# schematic.net
KiCad netlist of a schematic drawn in EasyEDA
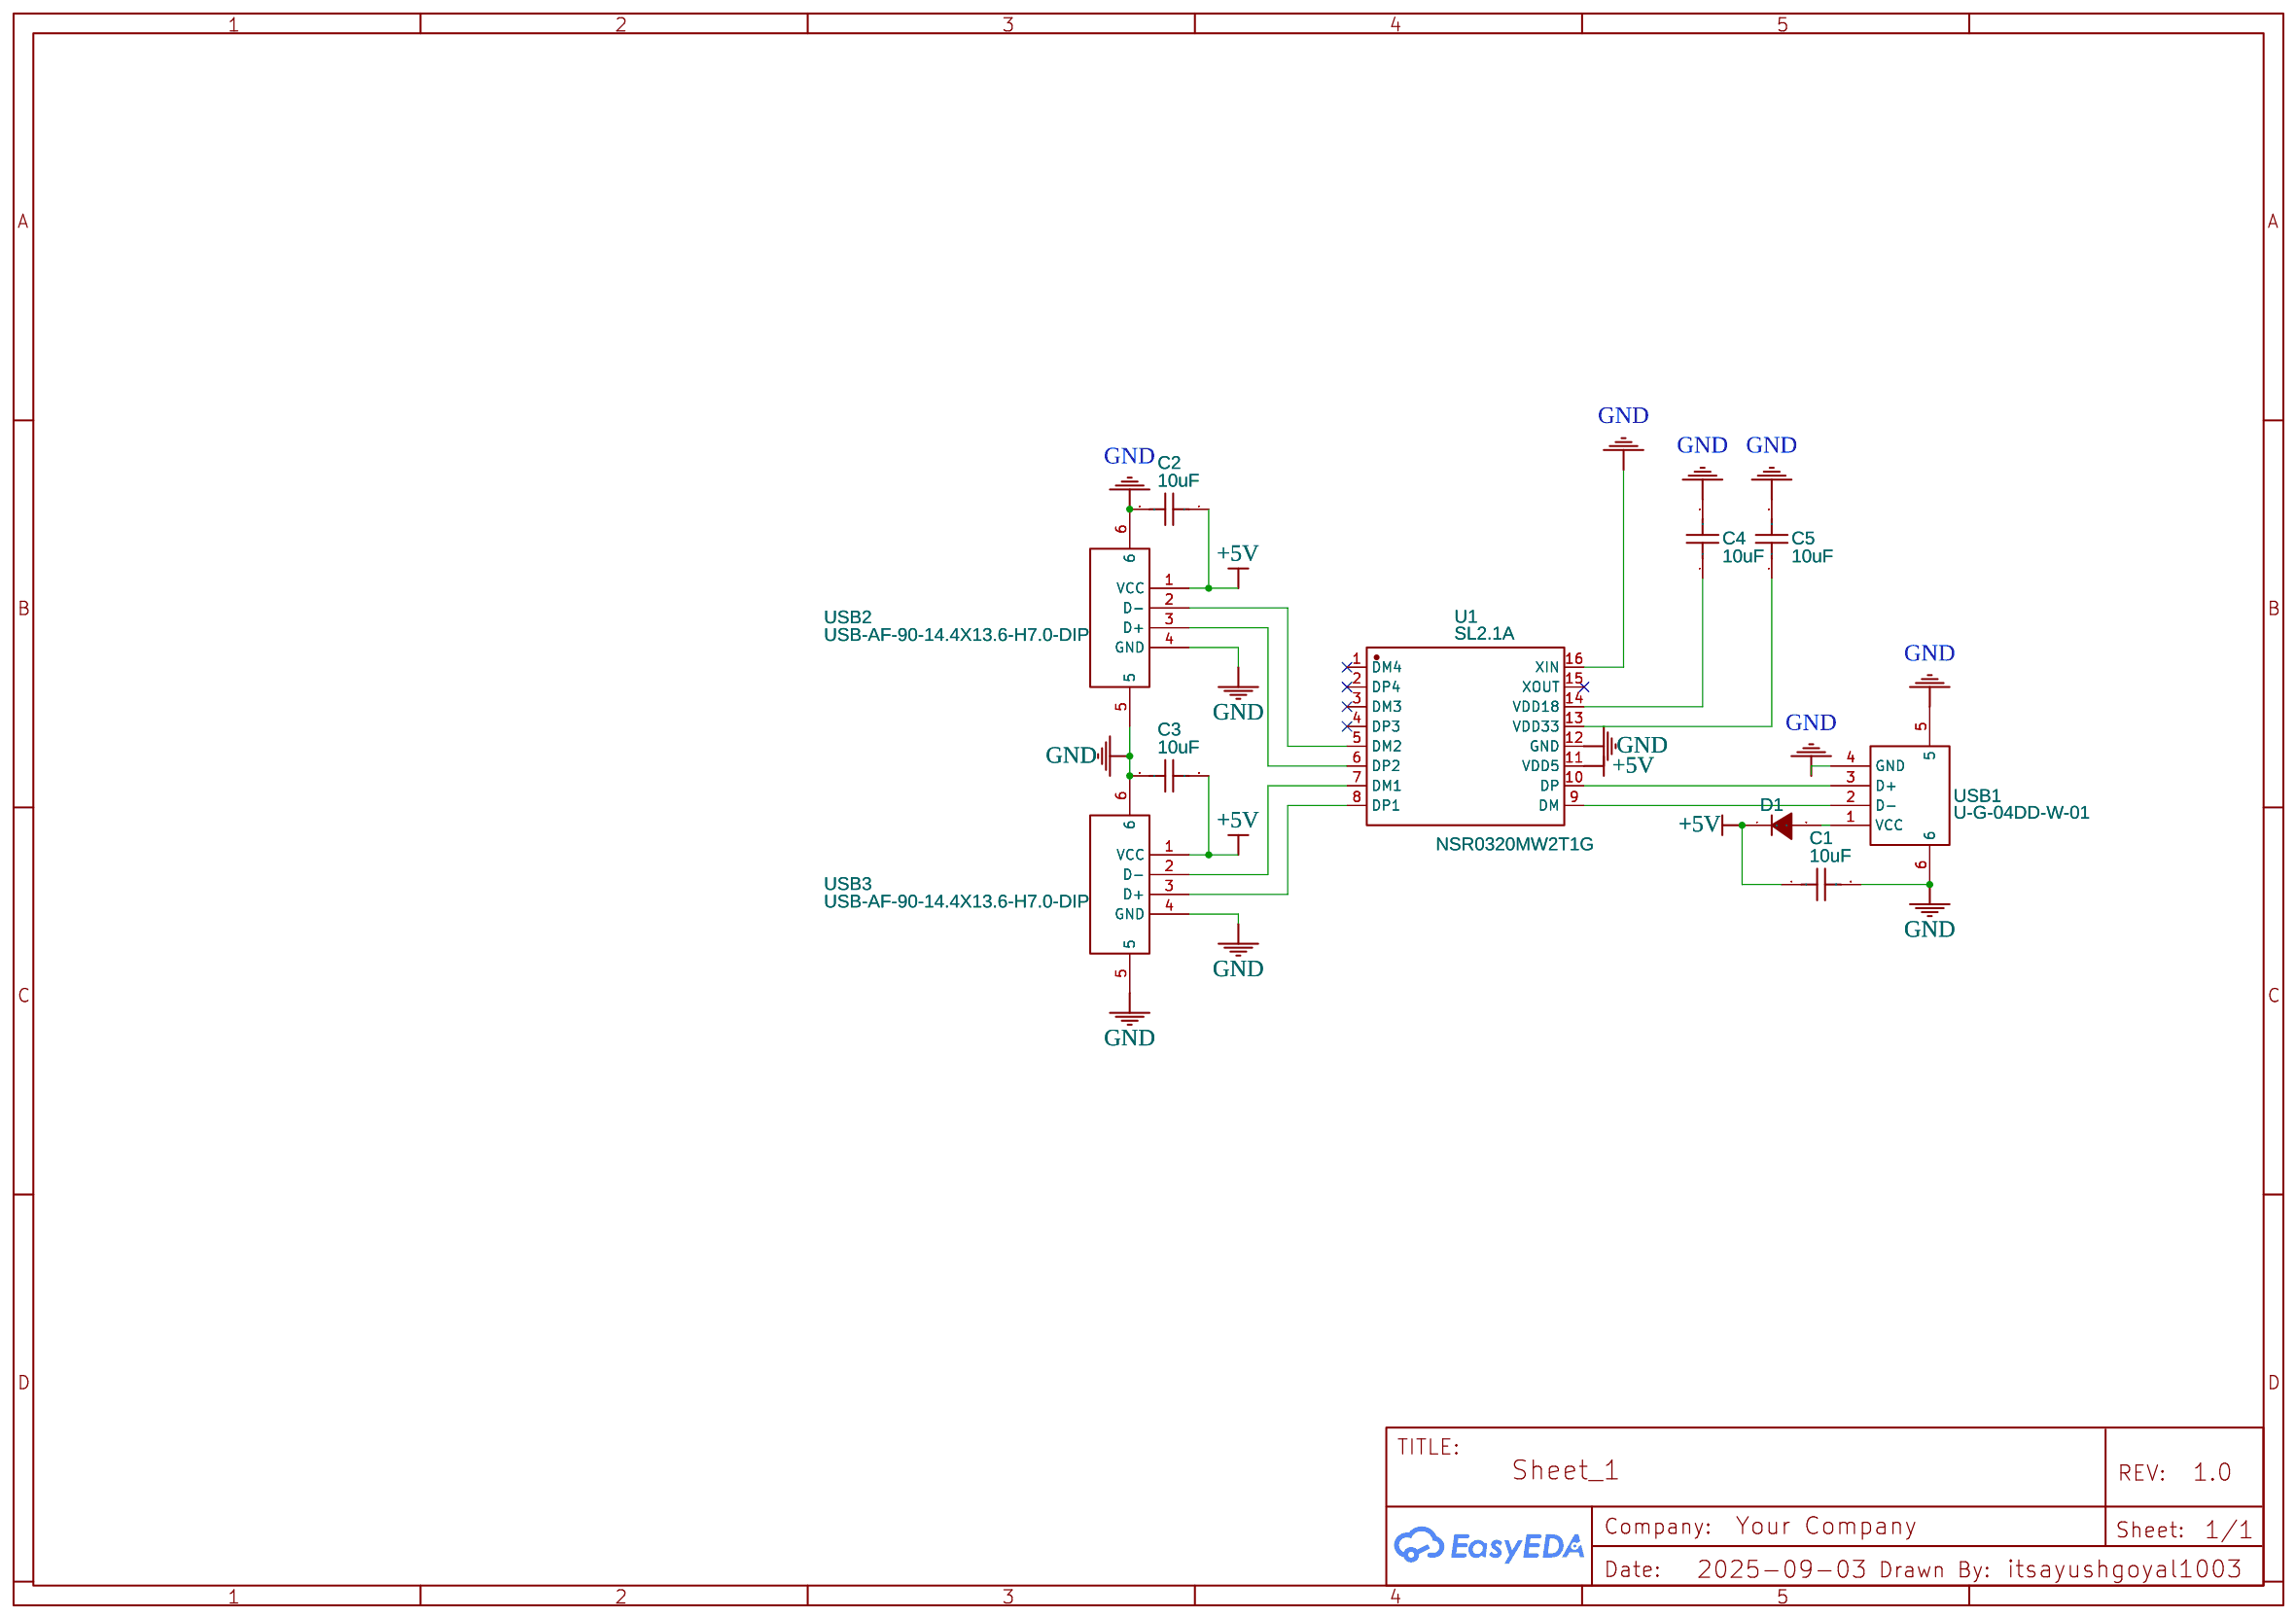
[diagram p0: schematic sheet]

(export (version "E")
  (design (tool "Eeschema 10.0.6"))
  (components
    (comp (ref "C1")
      (value "10uF")
      (fields
        (field (name "Manufacturer Part") "CL10A106KP8NNNC")
        (field (name "Manufacturer") "SAMSUNG(三星)")
      )
      (libsource (lib "") (part "CL10A106KP8NNNC"))
    )
    (comp (ref "C2")
      (value "10uF")
      (fields
        (field (name "Manufacturer Part") "CL10A106KP8NNNC")
        (field (name "Manufacturer") "SAMSUNG(三星)")
      )
      (libsource (lib "") (part "CL10A106KP8NNNC_1"))
    )
    (comp (ref "C3")
      (value "10uF")
      (fields
        (field (name "Manufacturer Part") "CL10A106KP8NNNC")
        (field (name "Manufacturer") "SAMSUNG(三星)")
      )
      (libsource (lib "") (part "CL10A106KP8NNNC"))
    )
    (comp (ref "C4")
      (value "10uF")
      (fields
        (field (name "Manufacturer Part") "CL10A106KP8NNNC")
        (field (name "Manufacturer") "SAMSUNG(三星)")
      )
      (libsource (lib "") (part "CL10A106KP8NNNC_2"))
    )
    (comp (ref "C5")
      (value "10uF")
      (fields
        (field (name "Manufacturer Part") "CL10A106KP8NNNC")
        (field (name "Manufacturer") "SAMSUNG(三星)")
      )
      (libsource (lib "") (part "CL10A106KP8NNNC_2"))
    )
    (comp (ref "D1")
      (value "NSR0320MW2T1G")
      (fields (field (name "Manufacturer") "onsemi(安森美)"))
      (libsource (lib "") (part "NSR0320MW2T1G"))
    )
    (comp (ref "U1")
      (value "SL2.1A")
      (fields (field (name "Manufacturer") "CoreChips(和芯润德)"))
      (libsource (lib "") (part "SL2.1A"))
    )
    (comp (ref "USB1")
      (value "U-G-04DD-W-01")
      (fields (field (name "Manufacturer Part") "U-G-O4DD-W-1") (field (name "Manufacturer") "韩国韩荣"))
      (libsource (lib "") (part "U-G-04DD-W-01"))
    )
    (comp (ref "USB2")
      (value "USB-AF-90-14.4X13.6-H7.0-DIP")
      (fields (field (name "Manufacturer Part") "903-131A1011D10100") (field (name "Manufacturer") "精拓金"))
      (libsource (lib "") (part "USB-AF-90-14.4X13.6-H7.0-DIP"))
    )
    (comp (ref "USB3")
      (value "USB-AF-90-14.4X13.6-H7.0-DIP")
      (fields (field (name "Manufacturer Part") "903-131A1011D10100") (field (name "Manufacturer") "精拓金"))
      (libsource (lib "") (part "USB-AF-90-14.4X13.6-H7.0-DIP"))
    )
  )
  (nets
    (net (code "1") (name "+5V") (class "Default")
      (node (ref "C1") (pin "1") (pinfunction "1_1") (pintype "unspecified"))
      (node (ref "C2") (pin "1") (pinfunction "1_1") (pintype "unspecified"))
      (node (ref "C3") (pin "2") (pinfunction "2_2") (pintype "unspecified"))
      (node (ref "D1") (pin "1") (pinfunction "C_1") (pintype "unspecified"))
      (node (ref "U1") (pin "11") (pinfunction "VDD5_11") (pintype "unspecified"))
      (node (ref "USB2") (pin "1") (pinfunction "VCC_1") (pintype "unspecified"))
      (node (ref "USB3") (pin "1") (pinfunction "VCC_1") (pintype "unspecified"))
    )
    (net (code "2") (name "GND") (class "Default")
      (node (ref "C1") (pin "2") (pinfunction "2_2") (pintype "unspecified"))
      (node (ref "C2") (pin "2") (pinfunction "2_2") (pintype "unspecified"))
      (node (ref "C3") (pin "1") (pinfunction "1_1") (pintype "unspecified"))
      (node (ref "C4") (pin "2") (pinfunction "2_2") (pintype "unspecified"))
      (node (ref "C5") (pin "2") (pinfunction "2_2") (pintype "unspecified"))
      (node (ref "U1") (pin "12") (pinfunction "GND_12") (pintype "unspecified"))
      (node (ref "U1") (pin "16") (pinfunction "XIN_16") (pintype "unspecified"))
      (node (ref "USB1") (pin "4") (pinfunction "GND_4") (pintype "unspecified"))
      (node (ref "USB1") (pin "5") (pinfunction "5_5") (pintype "unspecified"))
      (node (ref "USB1") (pin "6") (pinfunction "6_6") (pintype "unspecified"))
      (node (ref "USB2") (pin "4") (pinfunction "GND_4") (pintype "unspecified"))
      (node (ref "USB2") (pin "5") (pinfunction "5_5") (pintype "unspecified"))
      (node (ref "USB2") (pin "6") (pinfunction "6_6") (pintype "unspecified"))
      (node (ref "USB3") (pin "4") (pinfunction "GND_4") (pintype "unspecified"))
      (node (ref "USB3") (pin "5") (pinfunction "5_5") (pintype "unspecified"))
      (node (ref "USB3") (pin "6") (pinfunction "6_6") (pintype "unspecified"))
    )
    (net (code "3") (name "Net-(D1-A)") (class "Default")
      (node (ref "D1") (pin "2") (pinfunction "A_2") (pintype "unspecified"))
      (node (ref "USB1") (pin "1") (pinfunction "VCC_1") (pintype "unspecified"))
    )
    (net (code "4") (name "Net-(U1-DM)") (class "Default")
      (node (ref "U1") (pin "9") (pinfunction "DM_9") (pintype "unspecified"))
      (node (ref "USB1") (pin "2") (pinfunction "D-_2") (pintype "unspecified"))
    )
    (net (code "5") (name "Net-(U1-DM1)") (class "Default")
      (node (ref "U1") (pin "7") (pinfunction "DM1_7") (pintype "unspecified"))
      (node (ref "USB3") (pin "2") (pinfunction "D-_2") (pintype "unspecified"))
    )
    (net (code "6") (name "Net-(U1-DM2)") (class "Default")
      (node (ref "U1") (pin "5") (pinfunction "DM2_5") (pintype "unspecified"))
      (node (ref "USB2") (pin "2") (pinfunction "D-_2") (pintype "unspecified"))
    )
    (net (code "7") (name "Net-(U1-DP)") (class "Default")
      (node (ref "U1") (pin "10") (pinfunction "DP_10") (pintype "unspecified"))
      (node (ref "USB1") (pin "3") (pinfunction "D+_3") (pintype "unspecified"))
    )
    (net (code "8") (name "Net-(U1-DP1)") (class "Default")
      (node (ref "U1") (pin "8") (pinfunction "DP1_8") (pintype "unspecified"))
      (node (ref "USB3") (pin "3") (pinfunction "D+_3") (pintype "unspecified"))
    )
    (net (code "9") (name "Net-(U1-DP2)") (class "Default")
      (node (ref "U1") (pin "6") (pinfunction "DP2_6") (pintype "unspecified"))
      (node (ref "USB2") (pin "3") (pinfunction "D+_3") (pintype "unspecified"))
    )
    (net (code "10") (name "Net-(U1-VDD18)") (class "Default")
      (node (ref "C4") (pin "1") (pinfunction "1_1") (pintype "unspecified"))
      (node (ref "U1") (pin "14") (pinfunction "VDD18_14") (pintype "unspecified"))
    )
    (net (code "11") (name "Net-(U1-VDD33)") (class "Default")
      (node (ref "C5") (pin "1") (pinfunction "1_1") (pintype "unspecified"))
      (node (ref "U1") (pin "13") (pinfunction "VDD33_13") (pintype "unspecified"))
    )
    (net (code "12") (name "unconnected-(U1-DM3-Pad3)") (class "Default")
      (node (ref "U1") (pin "3") (pinfunction "DM3_3") (pintype "unspecified+no_connect"))
    )
    (net (code "13") (name "unconnected-(U1-DM4-Pad1)") (class "Default")
      (node (ref "U1") (pin "1") (pinfunction "DM4_1") (pintype "unspecified+no_connect"))
    )
    (net (code "14") (name "unconnected-(U1-DP3-Pad4)") (class "Default")
      (node (ref "U1") (pin "4") (pinfunction "DP3_4") (pintype "unspecified+no_connect"))
    )
    (net (code "15") (name "unconnected-(U1-DP4-Pad2)") (class "Default")
      (node (ref "U1") (pin "2") (pinfunction "DP4_2") (pintype "unspecified+no_connect"))
    )
    (net (code "16") (name "unconnected-(U1-XOUT-Pad15)") (class "Default")
      (node (ref "U1") (pin "15") (pinfunction "XOUT_15") (pintype "unspecified+no_connect"))
    )
  )
)
